# EEM_connector.net
KiCad netlist of a schematic drawn in Altium Designer
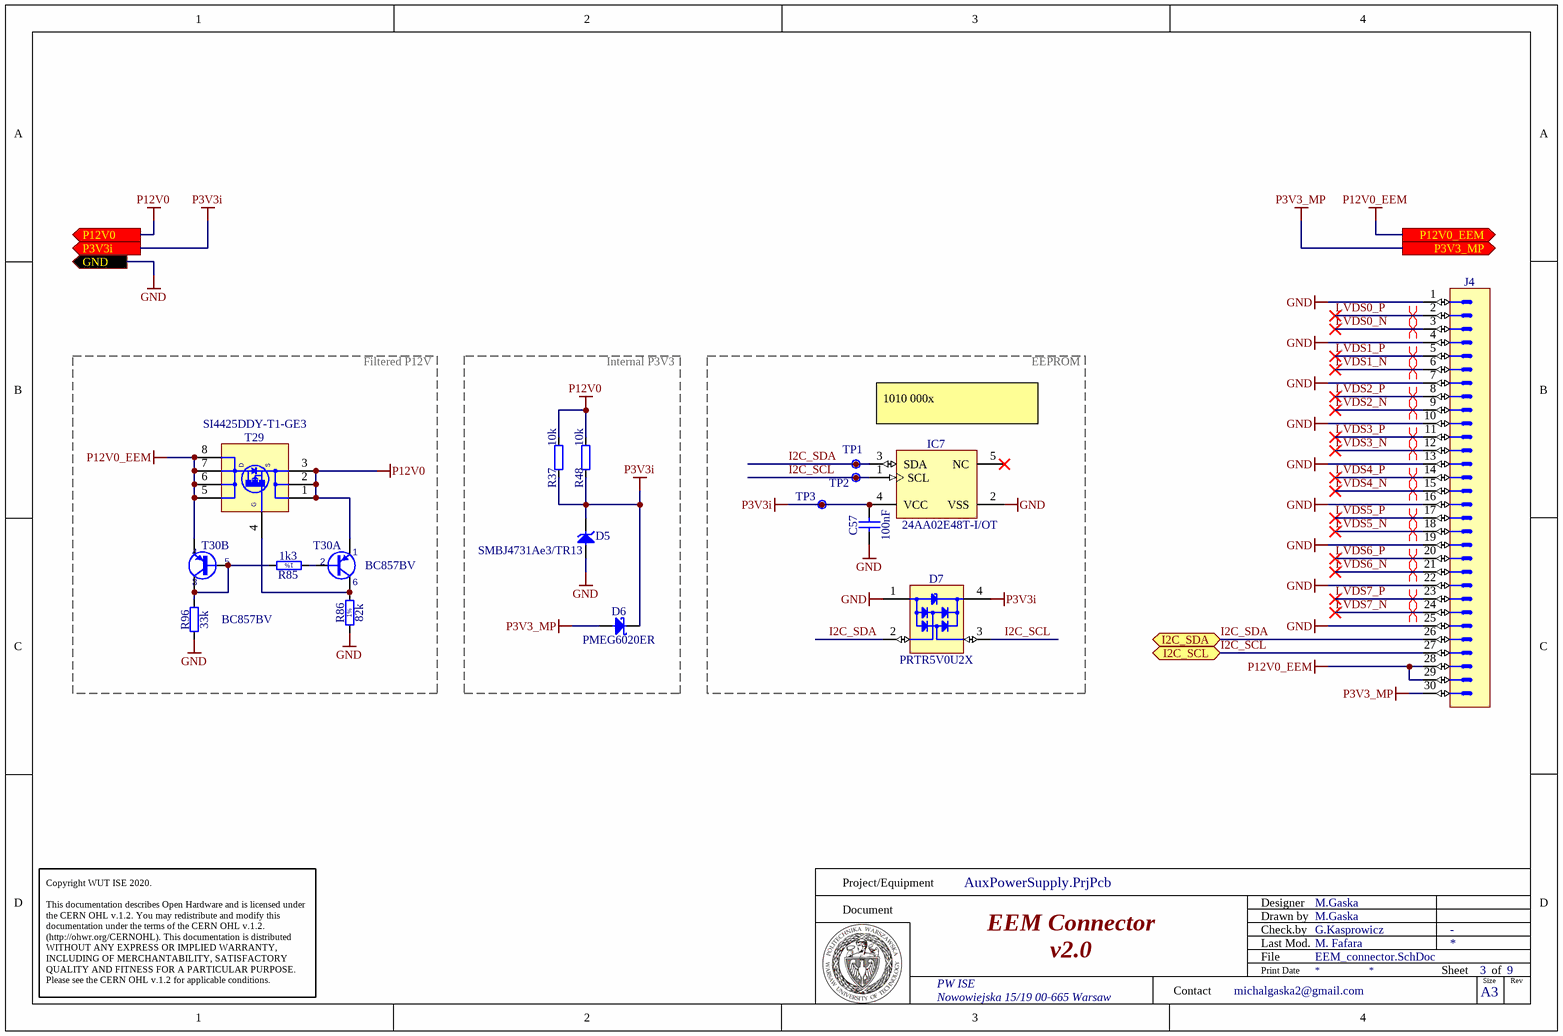
[diagram p0: EEM_connector.SchDoc]

(export (version "E")
  (design (tool "Eeschema 10.0.6"))
  (components
    (comp (ref "C57")
      (value "100nF")
      (footprint "CAPC1608X87N")
      (description "Non-polarised capacitor")
      (fields
        (field (name "PART NUMBER") "CC0603_100NF_50V_10%_X7R")
        (field (name "VOLTAGE") "50V")
        (field (name "AUTHOR") "CERN DEM JLC")
      )
      (libsource (lib "Capacitors") (part "Capacitor - non polarized"))
    )
    (comp (ref "D5")
      (value "SMBJ4731Ae3/TR13")
      (footprint "DIOM5436X244N")
      (description "Zener Diode 4.3V")
      (libsource (lib "Integrated_Library_MP") (part "SMBJ4731Ae3/TR13"))
    )
    (comp (ref "D6")
      (value "PMEG6020ER")
      (footprint "SODFL3517X110N")
      (description "Schottky Diode")
      (fields
        (field (name "VOLTAGE") "60V")
        (field (name "POWER") "2A")
        (field (name "AUTHOR") "CERN DEM JMW")
      )
      (libsource (lib "ICs And Semiconductors") (part "Diode Schottky"))
    )
    (comp (ref "D7")
      (value "PRTR5V0U2X")
      (footprint "SOT190P230X110-4N")
      (description "Ultra Low Capacitance Double Rail-to-Rail ESD Protection Diode")
      (fields
        (field (name "VOLTAGE") "5.5V")
        (field (name "MANUFACTURER") "NXP SEMICONDUCTORS")
        (field (name "AUTHOR") "CERN DEM JLC")
      )
      (libsource (lib "ICs And Semiconductors") (part "PRTR5V0U2X"))
    )
    (comp (ref "IC7")
      (value "24AA02E48T-I/OT")
      (footprint "SOT95P280X145-5N")
      (description "1.7V-5.5V, 2K I2C Serial EEPROM With EUI-48 Node Identity")
      (fields (field (name "MANUFACTURER") "MICROCHIP TECHNOLOGY") (field (name "AUTHOR") "CERN DEM MR"))
      (libsource (lib "ICs And Semiconductors") (part "24AA02E48T-I/OT"))
    )
    (comp (ref "J4")
      (value "~")
      (footprint "3M_N2530-6002RB")
      (description "Connector 30 Male")
      (fields
        (field (name "PART NUMBER") "3M_N2530-6002RB")
        (field (name "MANUFACTURER") "3M")
        (field (name "AUTHOR") "CERN DEM JLC")
      )
      (libsource (lib "Connectors") (part "Connector 30 Male"))
    )
    (comp (ref "R37")
      (value "10k")
      (footprint "RESC1608X55N")
      (description "Resistor - 1%")
      (fields
        (field (name "PART NUMBER") "R0603_10K_1%_0.1W_100PPM")
        (field (name "POWER") "0.1W")
        (field (name "AUTHOR") "CERN DEM JLC")
      )
      (libsource (lib "Resistors") (part "Resistor - 1%"))
    )
    (comp (ref "R48")
      (value "10k")
      (footprint "RESC1608X55N")
      (description "Resistor - 1%")
      (fields
        (field (name "PART NUMBER") "R0603_10K_1%_0.1W_100PPM")
        (field (name "POWER") "0.1W")
        (field (name "AUTHOR") "CERN DEM JLC")
      )
      (libsource (lib "Resistors") (part "Resistor - 1%"))
    )
    (comp (ref "R85")
      (value "1k3")
      (footprint "RESC1608X55N")
      (description "Resistor - 1%")
      (fields
        (field (name "PART NUMBER") "R0603_1K3_1%_0.1W_100PPM")
        (field (name "POWER") "0.1W")
        (field (name "AUTHOR") "CERN DEM JLC")
      )
      (libsource (lib "Resistors") (part "Resistor - 1%"))
    )
    (comp (ref "R86")
      (value "82k")
      (footprint "RESC1608X55N")
      (description "Resistor - 1%")
      (fields
        (field (name "PART NUMBER") "R0603_82K_1%_0.1W_100PPM")
        (field (name "POWER") "0.1W")
        (field (name "AUTHOR") "CERN DEM JLC")
      )
      (libsource (lib "Resistors") (part "Resistor - 1%"))
    )
    (comp (ref "R96")
      (value "33k")
      (footprint "RESC1608X55N")
      (description "Resistor - 1%")
      (fields
        (field (name "PART NUMBER") "R0603_33K_1%_0.1W_100PPM")
        (field (name "POWER") "0.1W")
        (field (name "AUTHOR") "CERN DEM JLC")
      )
      (libsource (lib "Resistors") (part "Resistor - 1%"))
    )
    (comp (ref "T29")
      (value "SI4425DDY-T1-GE3")
      (footprint "SOIC127P600X175-8N")
      (description "-30V -19.7A P-Channel MOSFET")
      (fields (field (name "MANUFACTURER") "VISHAY SILICONIX") (field (name "AUTHOR") "CERN DEM MR"))
      (libsource (lib "ICs And Semiconductors") (part "SI4425DDY"))
    )
    (comp (ref "T30")
      (value "BC857BV")
      (footprint "SOTFL50P160X60-6N")
      (description "45V, 100mA PNP General Purpose Double Transistor")
      (fields (field (name "MANUFACTURER") "NXP SEMICONDUCTORS") (field (name "AUTHOR") "CERN DEM JLC"))
      (libsource (lib "") (part "BC857BV_1"))
    )
    (comp (ref "TP1")
      (value "~")
      (footprint "TPS127")
      (description "Test Point")
      (fields (field (name "PART NUMBER") "SMD_PAD_1.27X1.27MM") (field (name "AUTHOR") "CERN DEM JLC"))
      (libsource (lib "Eletro-mechanical") (part "Test Point"))
    )
    (comp (ref "TP2")
      (value "~")
      (footprint "TPS127")
      (description "Test Point")
      (fields (field (name "PART NUMBER") "SMD_PAD_1.27X1.27MM") (field (name "AUTHOR") "CERN DEM JLC"))
      (libsource (lib "Eletro-mechanical") (part "Test Point"))
    )
    (comp (ref "TP3")
      (value "~")
      (footprint "TPS127")
      (description "Test Point")
      (fields (field (name "PART NUMBER") "SMD_PAD_1.27X1.27MM") (field (name "AUTHOR") "CERN DEM JLC"))
      (libsource (lib "Eletro-mechanical") (part "Test Point"))
    )
  )
  (nets
    (net (code "1") (name "/I2C_SCL") (class "Default")
      (node (ref "D7") (pin "3") (pinfunction "I/O2_3") (pintype "bidirectional"))
      (node (ref "IC7") (pin "1") (pinfunction "SCL_1") (pintype "input"))
      (node (ref "J4") (pin "27") (pinfunction "27_27") (pintype "bidirectional"))
      (node (ref "TP2") (pin "1") (pinfunction "1_1") (pintype "bidirectional"))
    )
    (net (code "2") (name "/I2C_SDA") (class "Default")
      (node (ref "D7") (pin "2") (pinfunction "I/O1_2") (pintype "bidirectional"))
      (node (ref "IC7") (pin "3") (pinfunction "SDA_3") (pintype "bidirectional"))
      (node (ref "J4") (pin "26") (pinfunction "26_26") (pintype "bidirectional"))
      (node (ref "TP1") (pin "1") (pinfunction "1_1") (pintype "bidirectional"))
    )
    (net (code "3") (name "/LVDS0_N") (class "Default")
      (node (ref "J4") (pin "3") (pinfunction "3_3") (pintype "bidirectional+no_connect"))
    )
    (net (code "4") (name "/LVDS0_P") (class "Default")
      (node (ref "J4") (pin "2") (pinfunction "2_2") (pintype "bidirectional+no_connect"))
    )
    (net (code "5") (name "/LVDS1_N") (class "Default")
      (node (ref "J4") (pin "6") (pinfunction "6_6") (pintype "bidirectional+no_connect"))
    )
    (net (code "6") (name "/LVDS1_P") (class "Default")
      (node (ref "J4") (pin "5") (pinfunction "5_5") (pintype "bidirectional+no_connect"))
    )
    (net (code "7") (name "/LVDS2_N") (class "Default")
      (node (ref "J4") (pin "9") (pinfunction "9_9") (pintype "bidirectional+no_connect"))
    )
    (net (code "8") (name "/LVDS2_P") (class "Default")
      (node (ref "J4") (pin "8") (pinfunction "8_8") (pintype "bidirectional+no_connect"))
    )
    (net (code "9") (name "/LVDS3_N") (class "Default")
      (node (ref "J4") (pin "12") (pinfunction "12_12") (pintype "bidirectional+no_connect"))
    )
    (net (code "10") (name "/LVDS3_P") (class "Default")
      (node (ref "J4") (pin "11") (pinfunction "11_11") (pintype "bidirectional+no_connect"))
    )
    (net (code "11") (name "/LVDS4_N") (class "Default")
      (node (ref "J4") (pin "15") (pinfunction "15_15") (pintype "bidirectional+no_connect"))
    )
    (net (code "12") (name "/LVDS4_P") (class "Default")
      (node (ref "J4") (pin "14") (pinfunction "14_14") (pintype "bidirectional+no_connect"))
    )
    (net (code "13") (name "/LVDS5_N") (class "Default")
      (node (ref "J4") (pin "18") (pinfunction "18_18") (pintype "bidirectional+no_connect"))
    )
    (net (code "14") (name "/LVDS5_P") (class "Default")
      (node (ref "J4") (pin "17") (pinfunction "17_17") (pintype "bidirectional+no_connect"))
    )
    (net (code "15") (name "/LVDS6_N") (class "Default")
      (node (ref "J4") (pin "21") (pinfunction "21_21") (pintype "bidirectional+no_connect"))
    )
    (net (code "16") (name "/LVDS6_P") (class "Default")
      (node (ref "J4") (pin "20") (pinfunction "20_20") (pintype "bidirectional+no_connect"))
    )
    (net (code "17") (name "/LVDS7_N") (class "Default")
      (node (ref "J4") (pin "24") (pinfunction "24_24") (pintype "bidirectional+no_connect"))
    )
    (net (code "18") (name "/LVDS7_P") (class "Default")
      (node (ref "J4") (pin "23") (pinfunction "23_23") (pintype "bidirectional+no_connect"))
    )
    (net (code "19") (name "GND") (class "Default")
      (node (ref "C57") (pin "1") (pinfunction "1_1") (pintype "passive"))
      (node (ref "D5") (pin "2") (pinfunction "A_2") (pintype "passive"))
      (node (ref "D7") (pin "1") (pinfunction "GND_1") (pintype "power_in"))
      (node (ref "IC7") (pin "2") (pinfunction "VSS_2") (pintype "power_in"))
      (node (ref "J4") (pin "1") (pinfunction "1_1") (pintype "bidirectional"))
      (node (ref "J4") (pin "10") (pinfunction "10_10") (pintype "bidirectional"))
      (node (ref "J4") (pin "13") (pinfunction "13_13") (pintype "bidirectional"))
      (node (ref "J4") (pin "16") (pinfunction "16_16") (pintype "bidirectional"))
      (node (ref "J4") (pin "19") (pinfunction "19_19") (pintype "bidirectional"))
      (node (ref "J4") (pin "22") (pinfunction "22_22") (pintype "bidirectional"))
      (node (ref "J4") (pin "25") (pinfunction "25_25") (pintype "bidirectional"))
      (node (ref "J4") (pin "4") (pinfunction "4_4") (pintype "bidirectional"))
      (node (ref "J4") (pin "7") (pinfunction "7_7") (pintype "bidirectional"))
      (node (ref "R86") (pin "1") (pinfunction "1_1") (pintype "passive"))
      (node (ref "R96") (pin "1") (pinfunction "1_1") (pintype "passive"))
    )
    (net (code "20") (name "Net-(T30A-B)") (class "Default")
      (node (ref "R85") (pin "1") (pinfunction "1_1") (pintype "passive"))
      (node (ref "T30") (pin "2") (pinfunction "B_2") (pintype "passive"))
    )
    (net (code "21") (name "Net-(T30A-C)") (class "Default")
      (node (ref "R86") (pin "2") (pinfunction "2_2") (pintype "passive"))
      (node (ref "T29") (pin "4") (pinfunction "S_4") (pintype "passive"))
      (node (ref "T30") (pin "6") (pinfunction "C_6") (pintype "passive"))
    )
    (net (code "22") (name "Net-(T30B-B)") (class "Default")
      (node (ref "R85") (pin "2") (pinfunction "2_2") (pintype "passive"))
      (node (ref "R96") (pin "2") (pinfunction "2_2") (pintype "passive"))
      (node (ref "T30") (pin "3") (pinfunction "C_3") (pintype "passive"))
      (node (ref "T30") (pin "5") (pinfunction "B_5") (pintype "passive"))
    )
    (net (code "23") (name "P3V3_MP") (class "Default")
      (node (ref "D6") (pin "2") (pinfunction "A_2") (pintype "passive"))
      (node (ref "J4") (pin "30") (pinfunction "30_30") (pintype "bidirectional"))
    )
    (net (code "24") (name "P3V3i") (class "Default")
      (node (ref "C57") (pin "2") (pinfunction "2_2") (pintype "passive"))
      (node (ref "D5") (pin "1") (pinfunction "C_1") (pintype "passive"))
      (node (ref "D6") (pin "1") (pinfunction "C_1") (pintype "passive"))
      (node (ref "D7") (pin "4") (pinfunction "VCC_4") (pintype "power_in"))
      (node (ref "IC7") (pin "4") (pinfunction "VCC_4") (pintype "power_in"))
      (node (ref "R37") (pin "1") (pinfunction "1_1") (pintype "passive"))
      (node (ref "R48") (pin "1") (pinfunction "1_1") (pintype "passive"))
      (node (ref "TP3") (pin "1") (pinfunction "1_1") (pintype "bidirectional"))
    )
    (net (code "25") (name "P12V0") (class "Default")
      (node (ref "R37") (pin "2") (pinfunction "2_2") (pintype "passive"))
      (node (ref "R48") (pin "2") (pinfunction "2_2") (pintype "passive"))
      (node (ref "T29") (pin "1") (pinfunction "S_1") (pintype "passive"))
      (node (ref "T29") (pin "2") (pinfunction "S_2") (pintype "passive"))
      (node (ref "T29") (pin "3") (pinfunction "S_3") (pintype "passive"))
      (node (ref "T30") (pin "1") (pinfunction "E_1") (pintype "passive"))
    )
    (net (code "26") (name "P12V0_EEM") (class "Default")
      (node (ref "J4") (pin "28") (pinfunction "28_28") (pintype "bidirectional"))
      (node (ref "J4") (pin "29") (pinfunction "29_29") (pintype "bidirectional"))
      (node (ref "T29") (pin "5") (pinfunction "D_5") (pintype "passive"))
      (node (ref "T29") (pin "6") (pinfunction "D_6") (pintype "passive"))
      (node (ref "T29") (pin "7") (pinfunction "D_7") (pintype "passive"))
      (node (ref "T29") (pin "8") (pinfunction "D_8") (pintype "passive"))
      (node (ref "T30") (pin "4") (pinfunction "E_4") (pintype "passive"))
    )
    (net (code "27") (name "unconnected-(IC7-NC-Pad5)") (class "Default")
      (node (ref "IC7") (pin "5") (pinfunction "NC_5") (pintype "passive+no_connect"))
    )
  )
)
